# 04_-_RP2040.net
KiCad netlist of a schematic drawn in Altium Designer
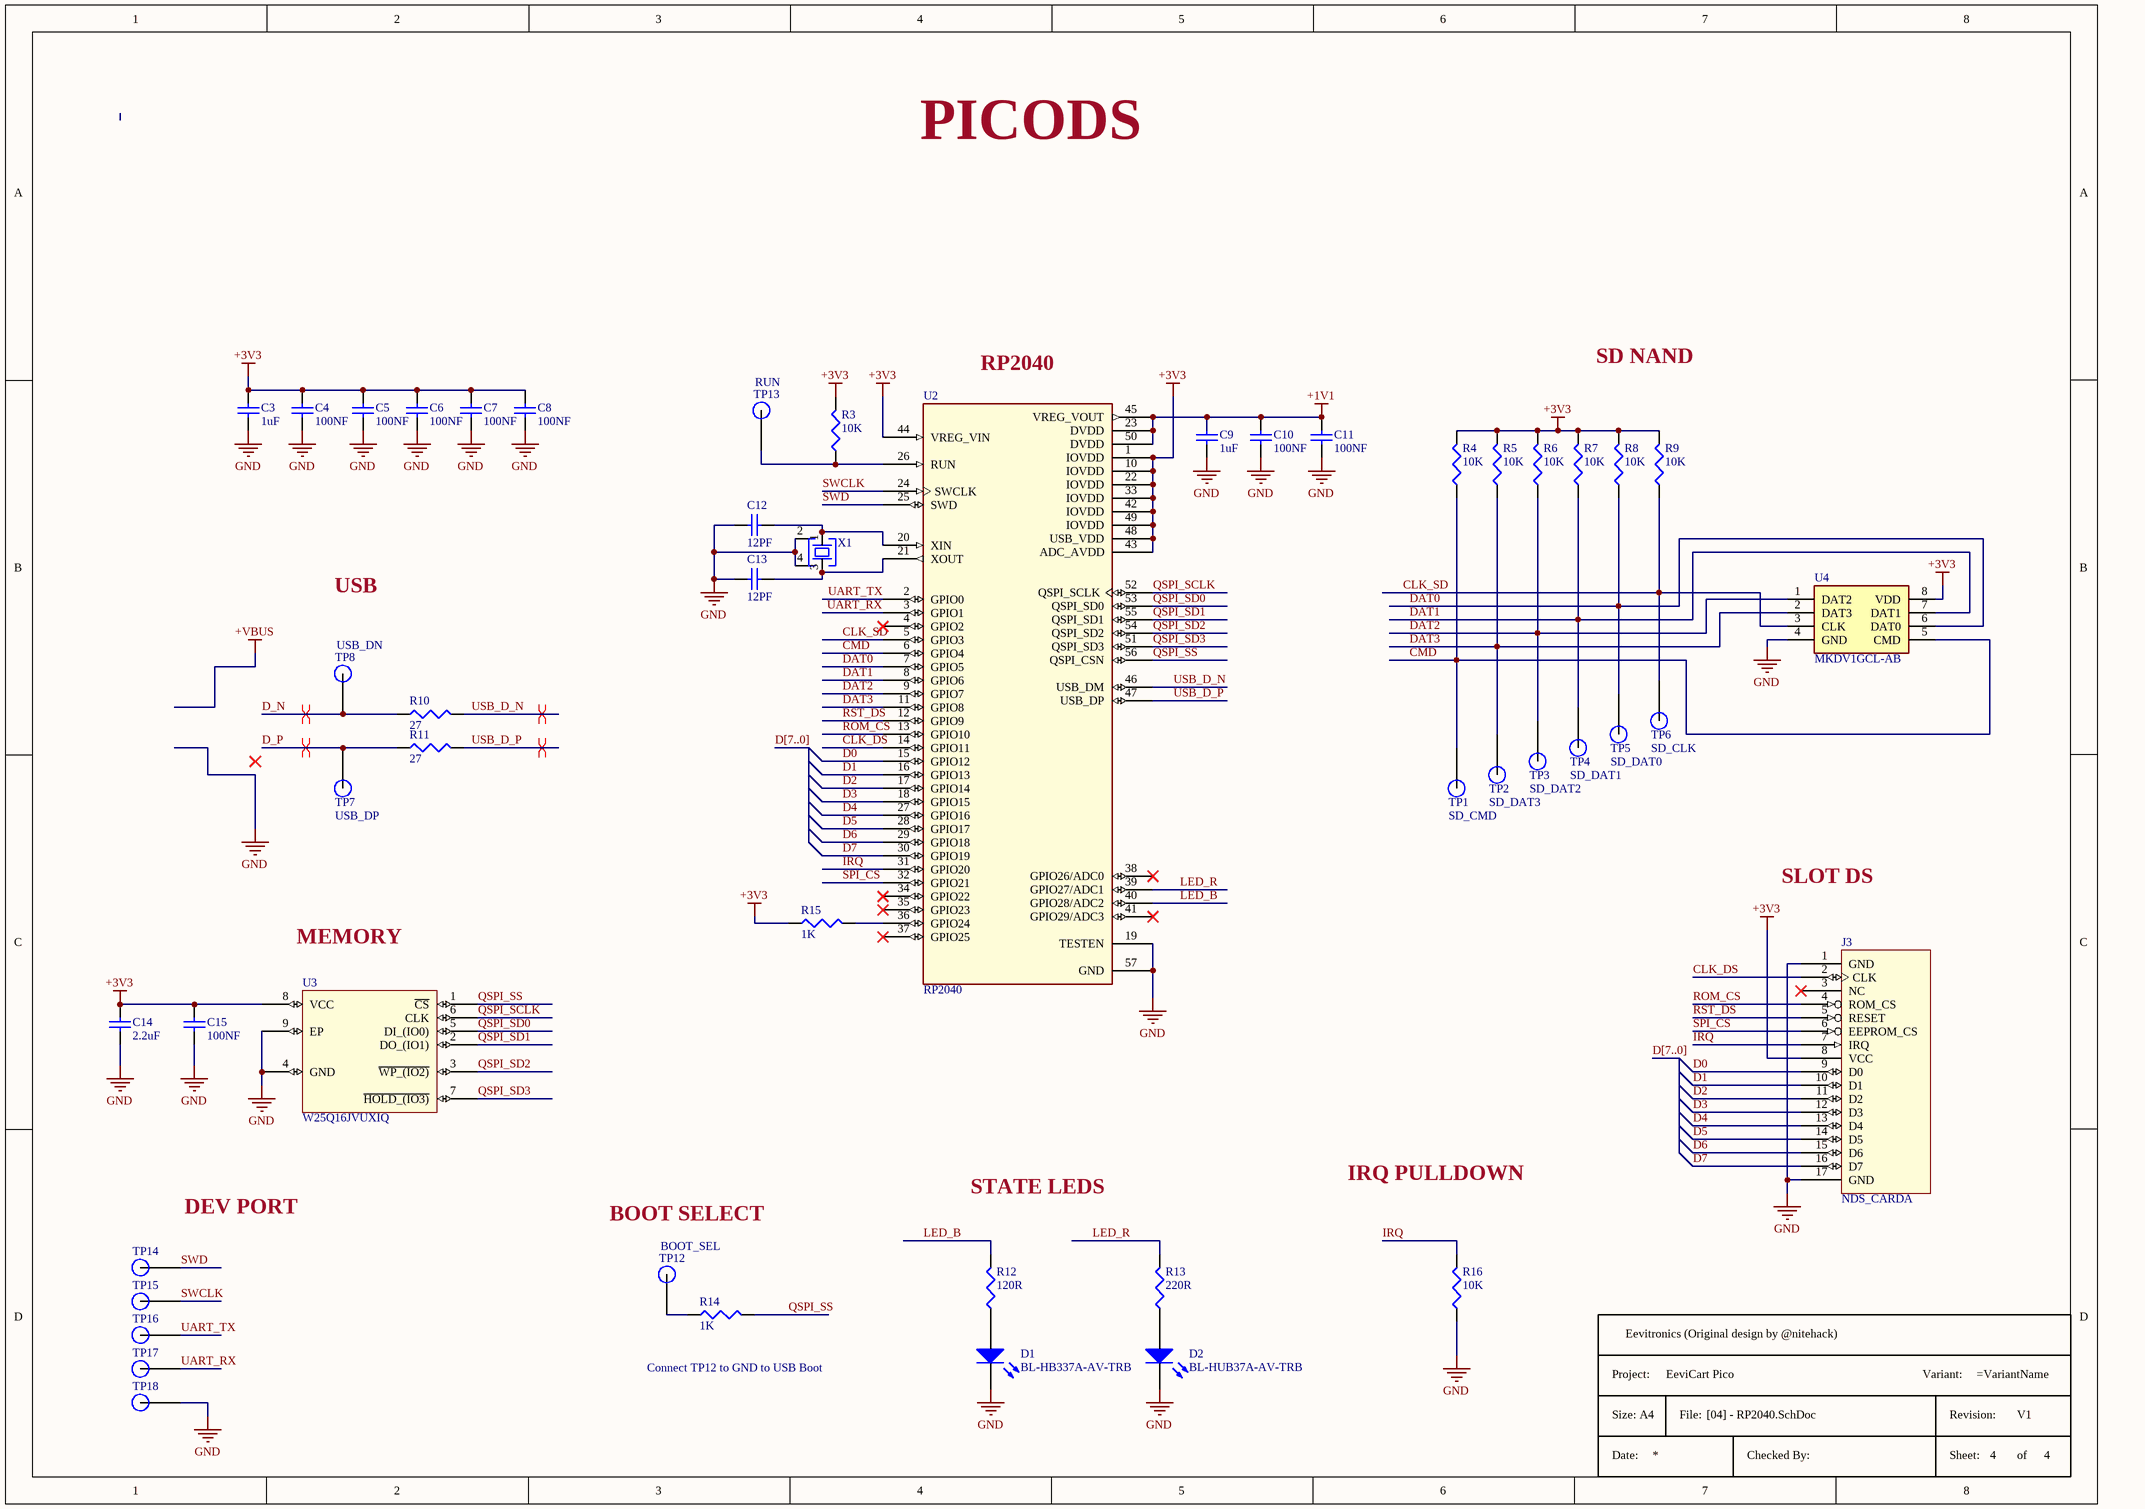
[diagram p0: [04] - RP2040.SchDoc]

(export (version "E")
  (design (tool "Eeschema 10.0.6"))
  (components
    (comp (ref "*") (value "Title Block A4") (libsource (lib "SCHLIB") (part "Title Block A4")))
    (comp (ref "C3")
      (value "1uF")
      (footprint "C0402")
      (description "TDK - C1005X5R1E105K050BC - COND, CERÁ MULT, X5R, 1UF, 25V, 0402")
      (fields
        (field (name "MANUFACTURER") "TDK")
        (field (name "MANUFACTURER PART NUMBER") "C1005X5R1E105K050BC")
      )
      (libsource (lib "SCHLIB") (part "C1005X5R1E105K050BC"))
    )
    (comp (ref "C4")
      (value "100NF")
      (footprint "C0402")
      (description "0402 0.1 uF 16V ±10 % Tolerance X7R SMT Multilayer Ceramic Capacitor")
      (fields
        (field (name "MANUFACTURER") "Murata")
        (field (name "MANUFACTURER PART NUMBER") "GRM155R71C104KA88D")
      )
      (libsource (lib "SCHLIB") (part "GRM155R71C104KA88D"))
    )
    (comp (ref "C5")
      (value "100NF")
      (footprint "C0402")
      (description "0402 0.1 uF 16V ±10 % Tolerance X7R SMT Multilayer Ceramic Capacitor")
      (fields
        (field (name "MANUFACTURER") "Murata")
        (field (name "MANUFACTURER PART NUMBER") "GRM155R71C104KA88D")
      )
      (libsource (lib "SCHLIB") (part "GRM155R71C104KA88D"))
    )
    (comp (ref "C6")
      (value "100NF")
      (footprint "C0402")
      (description "0402 0.1 uF 16V ±10 % Tolerance X7R SMT Multilayer Ceramic Capacitor")
      (fields
        (field (name "MANUFACTURER") "Murata")
        (field (name "MANUFACTURER PART NUMBER") "GRM155R71C104KA88D")
      )
      (libsource (lib "SCHLIB") (part "GRM155R71C104KA88D"))
    )
    (comp (ref "C7")
      (value "100NF")
      (footprint "C0402")
      (description "0402 0.1 uF 16V ±10 % Tolerance X7R SMT Multilayer Ceramic Capacitor")
      (fields
        (field (name "MANUFACTURER") "Murata")
        (field (name "MANUFACTURER PART NUMBER") "GRM155R71C104KA88D")
      )
      (libsource (lib "SCHLIB") (part "GRM155R71C104KA88D"))
    )
    (comp (ref "C8")
      (value "100NF")
      (footprint "C0402")
      (description "0402 0.1 uF 16V ±10 % Tolerance X7R SMT Multilayer Ceramic Capacitor")
      (fields
        (field (name "MANUFACTURER") "Murata")
        (field (name "MANUFACTURER PART NUMBER") "GRM155R71C104KA88D")
      )
      (libsource (lib "SCHLIB") (part "GRM155R71C104KA88D"))
    )
    (comp (ref "C9")
      (value "1uF")
      (footprint "C0402")
      (description "TDK - C1005X5R1E105K050BC - COND, CERÁ MULT, X5R, 1UF, 25V, 0402")
      (fields
        (field (name "MANUFACTURER") "TDK")
        (field (name "MANUFACTURER PART NUMBER") "C1005X5R1E105K050BC")
      )
      (libsource (lib "SCHLIB") (part "C1005X5R1E105K050BC"))
    )
    (comp (ref "C10")
      (value "100NF")
      (footprint "C0402")
      (description "0402 0.1 uF 16V ±10 % Tolerance X7R SMT Multilayer Ceramic Capacitor")
      (fields
        (field (name "MANUFACTURER") "Murata")
        (field (name "MANUFACTURER PART NUMBER") "GRM155R71C104KA88D")
      )
      (libsource (lib "SCHLIB") (part "GRM155R71C104KA88D"))
    )
    (comp (ref "C11")
      (value "100NF")
      (footprint "C0402")
      (description "0402 0.1 uF 16V ±10 % Tolerance X7R SMT Multilayer Ceramic Capacitor")
      (fields
        (field (name "MANUFACTURER") "Murata")
        (field (name "MANUFACTURER PART NUMBER") "GRM155R71C104KA88D")
      )
      (libsource (lib "SCHLIB") (part "GRM155R71C104KA88D"))
    )
    (comp (ref "C12")
      (value "12PF")
      (footprint "C0402")
      (description "CAP CER 12PF 50V C0G/NP0 0402")
      (fields
        (field (name "MANUFACTURER") "Kyocera AVX")
        (field (name "MANUFACTURER PART NUMBER") "04025A120JAT2A")
      )
      (libsource (lib "SCHLIB") (part "04025A120JAT2A"))
    )
    (comp (ref "C13")
      (value "12PF")
      (footprint "C0402")
      (description "CAP CER 12PF 50V C0G/NP0 0402")
      (fields
        (field (name "MANUFACTURER") "Kyocera AVX")
        (field (name "MANUFACTURER PART NUMBER") "04025A120JAT2A")
      )
      (libsource (lib "SCHLIB") (part "04025A120JAT2A"))
    )
    (comp (ref "C14")
      (value "2.2uF")
      (footprint "C0402")
      (description "TDK - C1005X5R1A225K050BC - COND, CERÁ MULT, X5R, 2.2UF, 10V, 0402")
      (fields
        (field (name "MANUFACTURER") "TDK")
        (field (name "MANUFACTURER PART NUMBER") "C1005X5R1A225K050BC")
        (field (name ".PCBCHECK") "VMM")
        (field (name ".SCHCHECK") "VMM")
      )
      (libsource (lib "SCHLIB") (part "C1005X5R1A225K050BC"))
    )
    (comp (ref "C15")
      (value "100NF")
      (footprint "C0402")
      (description "0402 0.1 uF 16V ±10 % Tolerance X7R SMT Multilayer Ceramic Capacitor")
      (fields
        (field (name "MANUFACTURER") "Murata")
        (field (name "MANUFACTURER PART NUMBER") "GRM155R71C104KA88D")
      )
      (libsource (lib "SCHLIB") (part "GRM155R71C104KA88D"))
    )
    (comp (ref "D1")
      (value "BL-HB337A-AV-TRB")
      (footprint "LED0402-RD")
      (description "Blue 0402 1X.5X4MM")
      (fields (field (name "MANUFACTURER") "American Bright"))
      (libsource (lib "SCHLIB") (part "BL-HB337A-AV-TRB"))
    )
    (comp (ref "D2")
      (value "BL-HUB37A-AV-TRB")
      (footprint "LED0402-RD")
      (description "Red 0402 1X.5X4MM")
      (fields (field (name "MANUFACTURER") "American Bright"))
      (libsource (lib "SCHLIB") (part "BL-HUB37A-AV-TRB"))
    )
    (comp (ref "J3") (value "NDS_CARDA") (footprint "NDS_CARD") (libsource (lib "SCHLIB") (part "NDS_CARDA")))
    (comp (ref "R3")
      (value "10K")
      (footprint "R0402")
      (description "VISHAY DRALORIC - CRCW040210K0FKED - RESISTENCIA, 10K, 0.063W, 1%, 0402, SMD")
      (fields
        (field (name "MANUFACTURER") "Vishay")
        (field (name "MANUFACTURER PART NUMBER") "CRCW040210K0FKED")
      )
      (libsource (lib "SCHLIB") (part "CRCW040210K0FKED"))
    )
    (comp (ref "R4")
      (value "10K")
      (footprint "R0402")
      (description "VISHAY DRALORIC - CRCW040210K0FKED - RESISTENCIA, 10K, 0.063W, 1%, 0402, SMD")
      (fields
        (field (name "MANUFACTURER") "Vishay")
        (field (name "MANUFACTURER PART NUMBER") "CRCW040210K0FKED")
      )
      (libsource (lib "SCHLIB") (part "CRCW040210K0FKED"))
    )
    (comp (ref "R5")
      (value "10K")
      (footprint "R0402")
      (description "VISHAY DRALORIC - CRCW040210K0FKED - RESISTENCIA, 10K, 0.063W, 1%, 0402, SMD")
      (fields
        (field (name "MANUFACTURER") "Vishay")
        (field (name "MANUFACTURER PART NUMBER") "CRCW040210K0FKED")
      )
      (libsource (lib "SCHLIB") (part "CRCW040210K0FKED"))
    )
    (comp (ref "R6")
      (value "10K")
      (footprint "R0402")
      (description "VISHAY DRALORIC - CRCW040210K0FKED - RESISTENCIA, 10K, 0.063W, 1%, 0402, SMD")
      (fields
        (field (name "MANUFACTURER") "Vishay")
        (field (name "MANUFACTURER PART NUMBER") "CRCW040210K0FKED")
      )
      (libsource (lib "SCHLIB") (part "CRCW040210K0FKED"))
    )
    (comp (ref "R7")
      (value "10K")
      (footprint "R0402")
      (description "VISHAY DRALORIC - CRCW040210K0FKED - RESISTENCIA, 10K, 0.063W, 1%, 0402, SMD")
      (fields
        (field (name "MANUFACTURER") "Vishay")
        (field (name "MANUFACTURER PART NUMBER") "CRCW040210K0FKED")
      )
      (libsource (lib "SCHLIB") (part "CRCW040210K0FKED"))
    )
    (comp (ref "R8")
      (value "10K")
      (footprint "R0402")
      (description "VISHAY DRALORIC - CRCW040210K0FKED - RESISTENCIA, 10K, 0.063W, 1%, 0402, SMD")
      (fields
        (field (name "MANUFACTURER") "Vishay")
        (field (name "MANUFACTURER PART NUMBER") "CRCW040210K0FKED")
      )
      (libsource (lib "SCHLIB") (part "CRCW040210K0FKED"))
    )
    (comp (ref "R9")
      (value "10K")
      (footprint "R0402")
      (description "VISHAY DRALORIC - CRCW040210K0FKED - RESISTENCIA, 10K, 0.063W, 1%, 0402, SMD")
      (fields
        (field (name "MANUFACTURER") "Vishay")
        (field (name "MANUFACTURER PART NUMBER") "CRCW040210K0FKED")
      )
      (libsource (lib "SCHLIB") (part "CRCW040210K0FKED"))
    )
    (comp (ref "R10")
      (value "27")
      (footprint "R0402")
      (description "RES 27 OHM 1% 1/16W 0402")
      (fields (field (name "TOLERANCE") "1%") (field (name "Comment") "RC0402FR-0727RL"))
      (libsource (lib "SCHLIB") (part "RC0402FR-0727RL"))
    )
    (comp (ref "R11")
      (value "27")
      (footprint "R0402")
      (description "RES 27 OHM 1% 1/16W 0402")
      (fields (field (name "TOLERANCE") "1%") (field (name "Comment") "RC0402FR-0727RL"))
      (libsource (lib "SCHLIB") (part "RC0402FR-0727RL"))
    )
    (comp (ref "R12")
      (value "120R")
      (footprint "R0402")
      (description "Res General Purpose Thick Film 0402 120 Ohm 1% 1/16W ±100ppm/°C Molded Paper T/R")
      (fields
        (field (name "MANUFACTURER") "Yageo")
        (field (name "MANUFACTURER PART NUMBER") "RC0402FR-07120RL")
      )
      (libsource (lib "SCHLIB") (part "RC0402FR-07120RL"))
    )
    (comp (ref "R13")
      (value "220R")
      (footprint "R0402")
      (description "SMD Chip Resistor, 220 Ohm, ± 1%, 62.5 mW, 0402 [1005 Metric], Thick Film, General Purpose")
      (fields
        (field (name "MANUFACTURER") "Yageo")
        (field (name "MANUFACTURER PART NUMBER") "RC0402FR-07220RL")
      )
      (libsource (lib "SCHLIB") (part "RC0402FR-07220RL"))
    )
    (comp (ref "R14")
      (value "1K")
      (footprint "R0402")
      (description "VISHAY - CRCW04021K00FKED - RES, PELÍC GRUESA, 1K, 1%, 0.063W, 0402")
      (fields
        (field (name "MANUFACTURER") "VISHAY")
        (field (name "MANUFACTURER PART NUMBER") "CRCW04021K00FKED")
      )
      (libsource (lib "SCHLIB") (part "CRCW04021K00FKEDC"))
    )
    (comp (ref "R15")
      (value "1K")
      (footprint "R0402")
      (description "VISHAY - CRCW04021K00FKED - RES, PELÍC GRUESA, 1K, 1%, 0.063W, 0402")
      (fields
        (field (name "MANUFACTURER") "VISHAY")
        (field (name "MANUFACTURER PART NUMBER") "CRCW04021K00FKED")
      )
      (libsource (lib "SCHLIB") (part "CRCW04021K00FKEDC"))
    )
    (comp (ref "R16")
      (value "10K")
      (footprint "R0402")
      (description "SMD Chip Resistor, 220 Ohm, ± 1%, 62.5 mW, 0402 [1005 Metric], Thick Film, General Purpose")
      (fields
        (field (name "MANUFACTURER") "Yageo")
        (field (name "MANUFACTURER PART NUMBER") "RC0402FR-07220RL")
      )
      (libsource (lib "SCHLIB") (part "RC0402FR-07220RL"))
    )
    (comp (ref "TP1")
      (value "SD_CMD")
      (footprint "Test Point")
      (libsource (lib "SCHLIB") (part "Test Point"))
    )
    (comp (ref "TP2")
      (value "SD_DAT3")
      (footprint "Test Point")
      (libsource (lib "SCHLIB") (part "Test Point"))
    )
    (comp (ref "TP3")
      (value "SD_DAT2")
      (footprint "Test Point")
      (libsource (lib "SCHLIB") (part "Test Point"))
    )
    (comp (ref "TP4")
      (value "SD_DAT1")
      (footprint "Test Point")
      (libsource (lib "SCHLIB") (part "Test Point"))
    )
    (comp (ref "TP5")
      (value "SD_DAT0")
      (footprint "Test Point")
      (libsource (lib "SCHLIB") (part "Test Point"))
    )
    (comp (ref "TP6")
      (value "SD_CLK")
      (footprint "Test Point")
      (libsource (lib "SCHLIB") (part "Test Point"))
    )
    (comp (ref "TP7")
      (value "USB_DP")
      (footprint "Test Point")
      (libsource (lib "SCHLIB") (part "Test Point"))
    )
    (comp (ref "TP8")
      (value "USB_DN")
      (footprint "Test Point")
      (libsource (lib "SCHLIB") (part "Test Point"))
    )
    (comp (ref "TP12")
      (value "BOOT_SEL")
      (footprint "Test Point")
      (libsource (lib "SCHLIB") (part "Test Point"))
    )
    (comp (ref "TP13") (value "RUN") (footprint "Test Point") (libsource (lib "SCHLIB") (part "Test Point")))
    (comp (ref "TP14") (value "~") (footprint "Test Point") (libsource (lib "SCHLIB") (part "Test Point")))
    (comp (ref "TP15") (value "~") (footprint "Test Point") (libsource (lib "SCHLIB") (part "Test Point")))
    (comp (ref "TP16") (value "~") (footprint "Test Point") (libsource (lib "SCHLIB") (part "Test Point")))
    (comp (ref "TP17") (value "~") (footprint "Test Point") (libsource (lib "SCHLIB") (part "Test Point")))
    (comp (ref "TP18") (value "~") (footprint "Test Point") (libsource (lib "SCHLIB") (part "Test Point")))
    (comp (ref "U2")
      (value "RP2040")
      (footprint "QFN40P700X700X90-57N")
      (description "RP2040 chip for Raspberry Pi Pico - ARM Cortex-M0+ MCU 32-Bit")
      (fields (field (name "MF") "Raspberry Pi"))
      (libsource (lib "SCHLIB") (part "RP2040"))
    )
    (comp (ref "U3")
      (value "W25Q16JVUXIQ")
      (footprint "SON50P300X200X60-9N")
      (description "NOR Flash Serial (SPI, Dual SPI, Quad SPI) 3V/3.3V 16M-bit 2M x 8 6ns 8-Pin USON EP T/R")
      (fields (field (name "MF") "Winbond"))
      (libsource (lib "SCHLIB") (part "W25Q16JVUXIQ"))
    )
    (comp (ref "U4")
      (value "MKDV1GCL-AB")
      (footprint "SamacSys:SON127P800X600X80-8N")
      (description "Integrated Circuit")
      (libsource (lib "SamacSys") (part "MKDV1GCL-AB"))
    )
    (comp (ref "X1")
      (value "XYDBPCNANF-12MHZ")
      (footprint "OSC-SMD_4P-L2.5-W2.0-BL")
      (libsource (lib "SCHLIB") (part "XYDBPCNANF-12MHZ"))
    )
  )
  (nets
    (net (code "1") (name "+1V1") (class "Default")
      (node (ref "C10") (pin "2") (pinfunction "2_2") (pintype "passive"))
      (node (ref "C11") (pin "2") (pinfunction "2_2") (pintype "passive"))
      (node (ref "C9") (pin "2") (pinfunction "2_2") (pintype "passive"))
      (node (ref "U2") (pin "23") (pinfunction "DVDD_23") (pintype "power_in"))
      (node (ref "U2") (pin "45") (pinfunction "VREG_VOUT_45") (pintype "output"))
      (node (ref "U2") (pin "50") (pinfunction "DVDD_50") (pintype "power_in"))
    )
    (net (code "2") (name "+3V3") (class "Default")
      (node (ref "C14") (pin "2") (pinfunction "2_2") (pintype "passive"))
      (node (ref "C15") (pin "2") (pinfunction "2_2") (pintype "passive"))
      (node (ref "C3") (pin "2") (pinfunction "2_2") (pintype "passive"))
      (node (ref "C4") (pin "2") (pinfunction "2_2") (pintype "passive"))
      (node (ref "C5") (pin "2") (pinfunction "2_2") (pintype "passive"))
      (node (ref "C6") (pin "2") (pinfunction "2_2") (pintype "passive"))
      (node (ref "C7") (pin "2") (pinfunction "2_2") (pintype "passive"))
      (node (ref "C8") (pin "2") (pinfunction "2_2") (pintype "passive"))
      (node (ref "J3") (pin "8") (pinfunction "VCC_8") (pintype "power_in"))
      (node (ref "R15") (pin "1") (pinfunction "1_1") (pintype "passive"))
      (node (ref "R3") (pin "2") (pinfunction "2_2") (pintype "passive"))
      (node (ref "R4") (pin "2") (pinfunction "2_2") (pintype "passive"))
      (node (ref "R5") (pin "2") (pinfunction "2_2") (pintype "passive"))
      (node (ref "R6") (pin "2") (pinfunction "2_2") (pintype "passive"))
      (node (ref "R7") (pin "2") (pinfunction "2_2") (pintype "passive"))
      (node (ref "R8") (pin "2") (pinfunction "2_2") (pintype "passive"))
      (node (ref "R9") (pin "2") (pinfunction "2_2") (pintype "passive"))
      (node (ref "U2") (pin "1") (pinfunction "IOVDD_1") (pintype "power_in"))
      (node (ref "U2") (pin "10") (pinfunction "IOVDD_10") (pintype "power_in"))
      (node (ref "U2") (pin "22") (pinfunction "IOVDD_22") (pintype "power_in"))
      (node (ref "U2") (pin "33") (pinfunction "IOVDD_33") (pintype "power_in"))
      (node (ref "U2") (pin "42") (pinfunction "IOVDD_42") (pintype "power_in"))
      (node (ref "U2") (pin "43") (pinfunction "ADC_AVDD_43") (pintype "power_in"))
      (node (ref "U2") (pin "44") (pinfunction "VREG_VIN_44") (pintype "input"))
      (node (ref "U2") (pin "48") (pinfunction "USB_VDD_48") (pintype "power_in"))
      (node (ref "U2") (pin "49") (pinfunction "IOVDD_49") (pintype "power_in"))
      (node (ref "U3") (pin "8") (pinfunction "VCC_8") (pintype "bidirectional"))
      (node (ref "U4") (pin "8") (pinfunction "VDD_8") (pintype "passive"))
    )
    (net (code "4") (name "/CLK_DS") (class "Default")
      (node (ref "J3") (pin "2") (pinfunction "CLK_2") (pintype "bidirectional"))
      (node (ref "U2") (pin "14") (pinfunction "GPIO11_14") (pintype "bidirectional"))
    )
    (net (code "5") (name "/CLK_SD") (class "Default")
      (node (ref "R9") (pin "1") (pinfunction "1_1") (pintype "passive"))
      (node (ref "TP6") (pin "1") (pinfunction "1_1") (pintype "passive"))
      (node (ref "U2") (pin "5") (pinfunction "GPIO3_5") (pintype "bidirectional"))
      (node (ref "U4") (pin "3") (pinfunction "CLK_3") (pintype "passive"))
    )
    (net (code "6") (name "/CMD") (class "Default")
      (node (ref "R4") (pin "1") (pinfunction "1_1") (pintype "passive"))
      (node (ref "TP1") (pin "1") (pinfunction "1_1") (pintype "passive"))
      (node (ref "U2") (pin "6") (pinfunction "GPIO4_6") (pintype "bidirectional"))
      (node (ref "U4") (pin "5") (pinfunction "CMD_5") (pintype "passive"))
    )
    (net (code "7") (name "/D0") (class "Default")
      (node (ref "J3") (pin "9") (pinfunction "D0_9") (pintype "bidirectional"))
      (node (ref "U2") (pin "15") (pinfunction "GPIO12_15") (pintype "bidirectional"))
    )
    (net (code "8") (name "/D1") (class "Default")
      (node (ref "J3") (pin "10") (pinfunction "D1_10") (pintype "bidirectional"))
      (node (ref "U2") (pin "16") (pinfunction "GPIO13_16") (pintype "bidirectional"))
    )
    (net (code "9") (name "/D2") (class "Default")
      (node (ref "J3") (pin "11") (pinfunction "D2_11") (pintype "bidirectional"))
      (node (ref "U2") (pin "17") (pinfunction "GPIO14_17") (pintype "bidirectional"))
    )
    (net (code "10") (name "/D3") (class "Default")
      (node (ref "J3") (pin "12") (pinfunction "D3_12") (pintype "bidirectional"))
      (node (ref "U2") (pin "18") (pinfunction "GPIO15_18") (pintype "bidirectional"))
    )
    (net (code "11") (name "/D4") (class "Default")
      (node (ref "J3") (pin "13") (pinfunction "D4_13") (pintype "bidirectional"))
      (node (ref "U2") (pin "27") (pinfunction "GPIO16_27") (pintype "bidirectional"))
    )
    (net (code "12") (name "/D5") (class "Default")
      (node (ref "J3") (pin "14") (pinfunction "D5_14") (pintype "bidirectional"))
      (node (ref "U2") (pin "28") (pinfunction "GPIO17_28") (pintype "bidirectional"))
    )
    (net (code "13") (name "/D6") (class "Default")
      (node (ref "J3") (pin "15") (pinfunction "D6_15") (pintype "bidirectional"))
      (node (ref "U2") (pin "29") (pinfunction "GPIO18_29") (pintype "bidirectional"))
    )
    (net (code "14") (name "/D7") (class "Default")
      (node (ref "J3") (pin "16") (pinfunction "D7_16") (pintype "bidirectional"))
      (node (ref "U2") (pin "30") (pinfunction "GPIO19_30") (pintype "bidirectional"))
    )
    (net (code "15") (name "/DAT0") (class "Default")
      (node (ref "R8") (pin "1") (pinfunction "1_1") (pintype "passive"))
      (node (ref "TP5") (pin "1") (pinfunction "1_1") (pintype "passive"))
      (node (ref "U2") (pin "7") (pinfunction "GPIO5_7") (pintype "bidirectional"))
      (node (ref "U4") (pin "6") (pinfunction "DAT0_6") (pintype "passive"))
    )
    (net (code "16") (name "/DAT1") (class "Default")
      (node (ref "R7") (pin "1") (pinfunction "1_1") (pintype "passive"))
      (node (ref "TP4") (pin "1") (pinfunction "1_1") (pintype "passive"))
      (node (ref "U2") (pin "8") (pinfunction "GPIO6_8") (pintype "bidirectional"))
      (node (ref "U4") (pin "7") (pinfunction "DAT1_7") (pintype "passive"))
    )
    (net (code "17") (name "/DAT2") (class "Default")
      (node (ref "R6") (pin "1") (pinfunction "1_1") (pintype "passive"))
      (node (ref "TP3") (pin "1") (pinfunction "1_1") (pintype "passive"))
      (node (ref "U2") (pin "9") (pinfunction "GPIO7_9") (pintype "bidirectional"))
      (node (ref "U4") (pin "1") (pinfunction "DAT2_1") (pintype "passive"))
    )
    (net (code "18") (name "/DAT3") (class "Default")
      (node (ref "R5") (pin "1") (pinfunction "1_1") (pintype "passive"))
      (node (ref "TP2") (pin "1") (pinfunction "1_1") (pintype "passive"))
      (node (ref "U2") (pin "11") (pinfunction "GPIO8_11") (pintype "bidirectional"))
      (node (ref "U4") (pin "2") (pinfunction "DAT3_2") (pintype "passive"))
    )
    (net (code "20") (name "/D_N") (class "Default")
      (node (ref "R10") (pin "1") (pinfunction "1_1") (pintype "passive"))
      (node (ref "TP8") (pin "1") (pinfunction "1_1") (pintype "passive"))
    )
    (net (code "21") (name "/D_P") (class "Default")
      (node (ref "R11") (pin "1") (pinfunction "1_1") (pintype "passive"))
      (node (ref "TP7") (pin "1") (pinfunction "1_1") (pintype "passive"))
    )
    (net (code "22") (name "/IRQ") (class "Default")
      (node (ref "J3") (pin "7") (pinfunction "IRQ_7") (pintype "input"))
      (node (ref "R16") (pin "2") (pinfunction "2_2") (pintype "passive"))
      (node (ref "U2") (pin "31") (pinfunction "GPIO20_31") (pintype "bidirectional"))
    )
    (net (code "23") (name "/LED_B") (class "Default")
      (node (ref "R12") (pin "2") (pinfunction "2_2") (pintype "passive"))
      (node (ref "U2") (pin "40") (pinfunction "GPIO28/ADC2_40") (pintype "bidirectional"))
    )
    (net (code "24") (name "/LED_R") (class "Default")
      (node (ref "R13") (pin "2") (pinfunction "2_2") (pintype "passive"))
      (node (ref "U2") (pin "39") (pinfunction "GPIO27/ADC1_39") (pintype "bidirectional"))
    )
    (net (code "25") (name "/QSPI_SCLK") (class "Default")
      (node (ref "U2") (pin "52") (pinfunction "QSPI_SCLK_52") (pintype "bidirectional"))
      (node (ref "U3") (pin "6") (pinfunction "CLK_6") (pintype "bidirectional"))
    )
    (net (code "26") (name "/QSPI_SD0") (class "Default")
      (node (ref "U2") (pin "53") (pinfunction "QSPI_SD0_53") (pintype "bidirectional"))
      (node (ref "U3") (pin "5") (pinfunction "DI_(IO0)_5") (pintype "bidirectional"))
    )
    (net (code "27") (name "/QSPI_SD1") (class "Default")
      (node (ref "U2") (pin "55") (pinfunction "QSPI_SD1_55") (pintype "bidirectional"))
      (node (ref "U3") (pin "2") (pinfunction "DO_(IO1)_2") (pintype "bidirectional"))
    )
    (net (code "28") (name "/QSPI_SD2") (class "Default")
      (node (ref "U2") (pin "54") (pinfunction "QSPI_SD2_54") (pintype "bidirectional"))
      (node (ref "U3") (pin "3") (pinfunction "~{WP_(IO2)}_3") (pintype "bidirectional"))
    )
    (net (code "29") (name "/QSPI_SD3") (class "Default")
      (node (ref "U2") (pin "51") (pinfunction "QSPI_SD3_51") (pintype "bidirectional"))
      (node (ref "U3") (pin "7") (pinfunction "~{HOLD_(IO3)}_7") (pintype "bidirectional"))
    )
    (net (code "30") (name "/QSPI_SS") (class "Default")
      (node (ref "R14") (pin "2") (pinfunction "2_2") (pintype "passive"))
      (node (ref "U2") (pin "56") (pinfunction "QSPI_CSN_56") (pintype "bidirectional"))
      (node (ref "U3") (pin "1") (pinfunction "~{CS}_1") (pintype "bidirectional"))
    )
    (net (code "31") (name "/ROM_CS") (class "Default")
      (node (ref "J3") (pin "4") (pinfunction "ROM_CS_4") (pintype "input"))
      (node (ref "U2") (pin "13") (pinfunction "GPIO10_13") (pintype "bidirectional"))
    )
    (net (code "32") (name "/RST_DS") (class "Default")
      (node (ref "J3") (pin "5") (pinfunction "RESET_5") (pintype "input"))
      (node (ref "U2") (pin "12") (pinfunction "GPIO9_12") (pintype "bidirectional"))
    )
    (net (code "33") (name "/SPI_CS") (class "Default")
      (node (ref "J3") (pin "6") (pinfunction "EEPROM_CS_6") (pintype "input"))
      (node (ref "U2") (pin "32") (pinfunction "GPIO21_32") (pintype "bidirectional"))
    )
    (net (code "34") (name "/SWCLK") (class "Default")
      (node (ref "TP15") (pin "1") (pinfunction "1_1") (pintype "passive"))
      (node (ref "U2") (pin "24") (pinfunction "SWCLK_24") (pintype "input"))
    )
    (net (code "35") (name "/SWD") (class "Default")
      (node (ref "TP14") (pin "1") (pinfunction "1_1") (pintype "passive"))
      (node (ref "U2") (pin "25") (pinfunction "SWD_25") (pintype "bidirectional"))
    )
    (net (code "36") (name "/UART_RX") (class "Default")
      (node (ref "TP17") (pin "1") (pinfunction "1_1") (pintype "passive"))
      (node (ref "U2") (pin "3") (pinfunction "GPIO1_3") (pintype "bidirectional"))
    )
    (net (code "37") (name "/UART_TX") (class "Default")
      (node (ref "TP16") (pin "1") (pinfunction "1_1") (pintype "passive"))
      (node (ref "U2") (pin "2") (pinfunction "GPIO0_2") (pintype "bidirectional"))
    )
    (net (code "38") (name "/USB_D_N") (class "Default")
      (node (ref "R10") (pin "2") (pinfunction "2_2") (pintype "passive"))
      (node (ref "U2") (pin "46") (pinfunction "USB_DM_46") (pintype "bidirectional"))
    )
    (net (code "39") (name "/USB_D_P") (class "Default")
      (node (ref "R11") (pin "2") (pinfunction "2_2") (pintype "passive"))
      (node (ref "U2") (pin "47") (pinfunction "USB_DP_47") (pintype "bidirectional"))
    )
    (net (code "40") (name "GND") (class "Default")
      (node (ref "C10") (pin "1") (pinfunction "1_1") (pintype "passive"))
      (node (ref "C11") (pin "1") (pinfunction "1_1") (pintype "passive"))
      (node (ref "C12") (pin "1") (pinfunction "1_1") (pintype "passive"))
      (node (ref "C13") (pin "1") (pinfunction "1_1") (pintype "passive"))
      (node (ref "C14") (pin "1") (pinfunction "1_1") (pintype "passive"))
      (node (ref "C15") (pin "1") (pinfunction "1_1") (pintype "passive"))
      (node (ref "C3") (pin "1") (pinfunction "1_1") (pintype "passive"))
      (node (ref "C4") (pin "1") (pinfunction "1_1") (pintype "passive"))
      (node (ref "C5") (pin "1") (pinfunction "1_1") (pintype "passive"))
      (node (ref "C6") (pin "1") (pinfunction "1_1") (pintype "passive"))
      (node (ref "C7") (pin "1") (pinfunction "1_1") (pintype "passive"))
      (node (ref "C8") (pin "1") (pinfunction "1_1") (pintype "passive"))
      (node (ref "C9") (pin "1") (pinfunction "1_1") (pintype "passive"))
      (node (ref "D1") (pin "1") (pinfunction "1_1") (pintype "passive"))
      (node (ref "D2") (pin "1") (pinfunction "1_1") (pintype "passive"))
      (node (ref "J3") (pin "1") (pinfunction "GND_1") (pintype "power_in"))
      (node (ref "J3") (pin "17") (pinfunction "GND_17") (pintype "power_in"))
      (node (ref "R16") (pin "1") (pinfunction "1_1") (pintype "passive"))
      (node (ref "TP18") (pin "1") (pinfunction "1_1") (pintype "passive"))
      (node (ref "U2") (pin "19") (pinfunction "TESTEN_19") (pintype "passive"))
      (node (ref "U2") (pin "57") (pinfunction "GND_57") (pintype "power_in"))
      (node (ref "U3") (pin "4") (pinfunction "GND_4") (pintype "bidirectional"))
      (node (ref "U3") (pin "9") (pinfunction "EP_9") (pintype "bidirectional"))
      (node (ref "U4") (pin "4") (pinfunction "GND_4") (pintype "passive"))
      (node (ref "X1") (pin "2") (pinfunction "2_2") (pintype "passive"))
      (node (ref "X1") (pin "4") (pinfunction "4_4") (pintype "passive"))
    )
    (net (code "41") (name "Net-(D1-Pad2)") (class "Default")
      (node (ref "D1") (pin "2") (pinfunction "2_2") (pintype "passive"))
      (node (ref "R12") (pin "1") (pinfunction "1_1") (pintype "passive"))
    )
    (net (code "42") (name "Net-(D2-Pad2)") (class "Default")
      (node (ref "D2") (pin "2") (pinfunction "2_2") (pintype "passive"))
      (node (ref "R13") (pin "1") (pinfunction "1_1") (pintype "passive"))
    )
    (net (code "43") (name "Net-(R14-Pad1)") (class "Default")
      (node (ref "R14") (pin "1") (pinfunction "1_1") (pintype "passive"))
      (node (ref "TP12") (pin "1") (pinfunction "1_1") (pintype "passive"))
    )
    (net (code "44") (name "Net-(U2-GPIO24)") (class "Default")
      (node (ref "R15") (pin "2") (pinfunction "2_2") (pintype "passive"))
      (node (ref "U2") (pin "36") (pinfunction "GPIO24_36") (pintype "bidirectional"))
    )
    (net (code "45") (name "Net-(U2-RUN)") (class "Default")
      (node (ref "R3") (pin "1") (pinfunction "1_1") (pintype "passive"))
      (node (ref "TP13") (pin "1") (pinfunction "1_1") (pintype "passive"))
      (node (ref "U2") (pin "26") (pinfunction "RUN_26") (pintype "input"))
    )
    (net (code "46") (name "Net-(U2-XIN)") (class "Default")
      (node (ref "C12") (pin "2") (pinfunction "2_2") (pintype "passive"))
      (node (ref "U2") (pin "20") (pinfunction "XIN_20") (pintype "input"))
      (node (ref "X1") (pin "1") (pinfunction "1_1") (pintype "passive"))
    )
    (net (code "47") (name "Net-(U2-XOUT)") (class "Default")
      (node (ref "C13") (pin "2") (pinfunction "2_2") (pintype "passive"))
      (node (ref "U2") (pin "21") (pinfunction "XOUT_21") (pintype "output"))
      (node (ref "X1") (pin "3") (pinfunction "3_3") (pintype "passive"))
    )
    (net (code "48") (name "unconnected-(J3-NC-Pad3)") (class "Default")
      (node (ref "J3") (pin "3") (pinfunction "NC_3") (pintype "passive+no_connect"))
    )
    (net (code "49") (name "unconnected-(U2-GPIO2-Pad4)") (class "Default")
      (node (ref "U2") (pin "4") (pinfunction "GPIO2_4") (pintype "bidirectional+no_connect"))
    )
    (net (code "50") (name "unconnected-(U2-GPIO22-Pad34)") (class "Default")
      (node (ref "U2") (pin "34") (pinfunction "GPIO22_34") (pintype "bidirectional+no_connect"))
    )
    (net (code "51") (name "unconnected-(U2-GPIO23-Pad35)") (class "Default")
      (node (ref "U2") (pin "35") (pinfunction "GPIO23_35") (pintype "bidirectional+no_connect"))
    )
    (net (code "52") (name "unconnected-(U2-GPIO25-Pad37)") (class "Default")
      (node (ref "U2") (pin "37") (pinfunction "GPIO25_37") (pintype "bidirectional+no_connect"))
    )
    (net (code "53") (name "unconnected-(U2-GPIO26{slash}ADC0-Pad38)") (class "Default")
      (node (ref "U2") (pin "38") (pinfunction "GPIO26/ADC0_38") (pintype "bidirectional+no_connect"))
    )
    (net (code "54") (name "unconnected-(U2-GPIO29{slash}ADC3-Pad41)") (class "Default")
      (node (ref "U2") (pin "41") (pinfunction "GPIO29/ADC3_41") (pintype "bidirectional+no_connect"))
    )
  )
)
